# bionic_glove_1_01.net
KiCad netlist of a schematic drawn in EAGLE
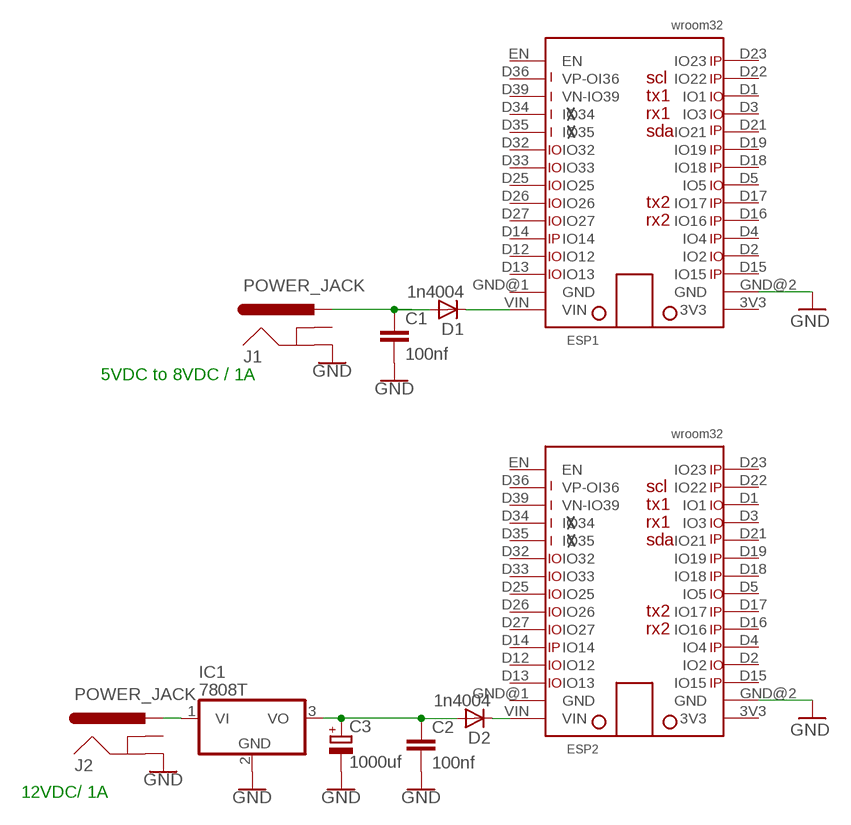
[diagram p0: schematic, sheet 1]

(export (version "E")
  (design (tool "Eeschema 10.0.6"))
  (components
    (comp (ref "C1")
      (value "100nf")
      (footprint "eagle-import:C1206")
      (libsource (lib "eagle-import") (part "CAPACITORC1206"))
    )
    (comp (ref "C2")
      (value "100nf")
      (footprint "eagle-import:C1206")
      (libsource (lib "eagle-import") (part "CAPACITORC1206"))
    )
    (comp (ref "C3")
      (value "1000uf")
      (footprint "eagle-import:E2,5-5")
      (libsource (lib "eagle-import") (part "CPOL-EUE2.5-5"))
    )
    (comp (ref "D1")
      (value "1n4004")
      (footprint "eagle-import:DIODE_DO35-7")
      (libsource (lib "eagle-import") (part "DIODE_E-DO35-7"))
    )
    (comp (ref "D2")
      (value "1n4004")
      (footprint "eagle-import:DIODE_DO35-7")
      (libsource (lib "eagle-import") (part "DIODE_E-DO35-7"))
    )
    (comp (ref "ESP1")
      (value "wroom32")
      (footprint "eagle-import:ESP32-DEVKITV1")
      (libsource (lib "eagle-import") (part "ESP32DEVKITV1"))
    )
    (comp (ref "ESP2")
      (value "wroom32")
      (footprint "eagle-import:ESP32-DEVKITV1")
      (libsource (lib "eagle-import") (part "ESP32DEVKITV1"))
    )
    (comp (ref "IC1")
      (value "7808T")
      (footprint "eagle-import:TO220H")
      (libsource (lib "eagle-import") (part "78T08"))
    )
    (comp (ref "J1")
      (value "POWER_JACK")
      (footprint "eagle-import:POWER_JACK_PTH")
      (libsource (lib "eagle-import") (part "POWER_JACK"))
    )
    (comp (ref "J2")
      (value "POWER_JACK")
      (footprint "eagle-import:POWER_JACK_PTH")
      (libsource (lib "eagle-import") (part "POWER_JACK"))
    )
  )
  (nets
    (net (code "1") (name "GND") (class "Default")
      (node (ref "C1") (pin "2") (pinfunction "2_2") (pintype "passive"))
      (node (ref "C2") (pin "2") (pinfunction "2_2") (pintype "passive"))
      (node (ref "C3") (pin "-") (pinfunction "-_-") (pintype "passive"))
      (node (ref "ESP1") (pin "GND@2") (pinfunction "GND_GND@2") (pintype "bidirectional"))
      (node (ref "ESP2") (pin "GND@2") (pinfunction "GND_GND@2") (pintype "bidirectional"))
      (node (ref "IC1") (pin "2") (pinfunction "GND_2") (pintype "passive"))
      (node (ref "J1") (pin "GND") (pinfunction "GND_GND") (pintype "bidirectional"))
      (node (ref "J2") (pin "GND") (pinfunction "GND_GND") (pintype "bidirectional"))
    )
    (net (code "2") (name "Net-(D1-A)") (class "Default")
      (node (ref "D1") (pin "C") (pinfunction "A_C") (pintype "passive"))
      (node (ref "ESP1") (pin "VIN") (pinfunction "VIN_VIN") (pintype "bidirectional"))
    )
    (net (code "3") (name "Net-(D1-C)") (class "Default")
      (node (ref "C1") (pin "1") (pinfunction "1_1") (pintype "passive"))
      (node (ref "D1") (pin "A") (pinfunction "C_A") (pintype "passive"))
      (node (ref "J1") (pin "PWR") (pinfunction "PWR_PWR") (pintype "bidirectional"))
    )
    (net (code "4") (name "Net-(D2-A)") (class "Default")
      (node (ref "D2") (pin "C") (pinfunction "A_C") (pintype "passive"))
      (node (ref "ESP2") (pin "VIN") (pinfunction "VIN_VIN") (pintype "bidirectional"))
    )
    (net (code "5") (name "Net-(D2-C)") (class "Default")
      (node (ref "C2") (pin "1") (pinfunction "1_1") (pintype "passive"))
      (node (ref "C3") (pin "+") (pinfunction "+_+") (pintype "passive"))
      (node (ref "D2") (pin "A") (pinfunction "C_A") (pintype "passive"))
      (node (ref "IC1") (pin "3") (pinfunction "VO_3") (pintype "passive"))
    )
    (net (code "6") (name "Net-(IC1-VI)") (class "Default")
      (node (ref "IC1") (pin "1") (pinfunction "VI_1") (pintype "input"))
      (node (ref "J2") (pin "PWR") (pinfunction "PWR_PWR") (pintype "bidirectional"))
    )
    (net (code "7") (name "unconnected-(ESP1-GND-PadGND@1)") (class "Default")
      (node (ref "ESP1") (pin "GND@1") (pinfunction "GND_GND@1") (pintype "bidirectional"))
    )
    (net (code "8") (name "unconnected-(ESP1-IO1-PadD1)") (class "Default")
      (node (ref "ESP1") (pin "D1") (pinfunction "IO1_D1") (pintype "bidirectional"))
    )
    (net (code "9") (name "unconnected-(ESP1-IO2-PadD2)") (class "Default")
      (node (ref "ESP1") (pin "D2") (pinfunction "IO2_D2") (pintype "bidirectional"))
    )
    (net (code "10") (name "unconnected-(ESP1-IO3-PadD3)") (class "Default")
      (node (ref "ESP1") (pin "D3") (pinfunction "IO3_D3") (pintype "bidirectional"))
    )
    (net (code "11") (name "unconnected-(ESP1-IO4-PadD4)") (class "Default")
      (node (ref "ESP1") (pin "D4") (pinfunction "IO4_D4") (pintype "bidirectional"))
    )
    (net (code "12") (name "unconnected-(ESP1-IO5-PadD5)") (class "Default")
      (node (ref "ESP1") (pin "D5") (pinfunction "IO5_D5") (pintype "bidirectional"))
    )
    (net (code "13") (name "unconnected-(ESP1-IO12-PadD12)") (class "Default")
      (node (ref "ESP1") (pin "D12") (pinfunction "IO12_D12") (pintype "bidirectional"))
    )
    (net (code "14") (name "unconnected-(ESP1-IO13-PadD13)") (class "Default")
      (node (ref "ESP1") (pin "D13") (pinfunction "IO13_D13") (pintype "bidirectional"))
    )
    (net (code "15") (name "unconnected-(ESP1-IO14-PadD14)") (class "Default")
      (node (ref "ESP1") (pin "D14") (pinfunction "IO14_D14") (pintype "bidirectional"))
    )
    (net (code "16") (name "unconnected-(ESP1-IO15-PadD15)") (class "Default")
      (node (ref "ESP1") (pin "D15") (pinfunction "IO15_D15") (pintype "bidirectional"))
    )
    (net (code "17") (name "unconnected-(ESP1-IO16-PadD16)") (class "Default")
      (node (ref "ESP1") (pin "D16") (pinfunction "IO16_D16") (pintype "bidirectional"))
    )
    (net (code "18") (name "unconnected-(ESP1-IO17-PadD17)") (class "Default")
      (node (ref "ESP1") (pin "D17") (pinfunction "IO17_D17") (pintype "bidirectional"))
    )
    (net (code "19") (name "unconnected-(ESP1-IO18-PadD18)") (class "Default")
      (node (ref "ESP1") (pin "D18") (pinfunction "IO18_D18") (pintype "bidirectional"))
    )
    (net (code "20") (name "unconnected-(ESP1-IO19-PadD19)") (class "Default")
      (node (ref "ESP1") (pin "D19") (pinfunction "IO19_D19") (pintype "bidirectional"))
    )
    (net (code "21") (name "unconnected-(ESP1-IO21-PadD21)") (class "Default")
      (node (ref "ESP1") (pin "D21") (pinfunction "IO21_D21") (pintype "bidirectional"))
    )
    (net (code "22") (name "unconnected-(ESP1-IO22-PadD22)") (class "Default")
      (node (ref "ESP1") (pin "D22") (pinfunction "IO22_D22") (pintype "bidirectional"))
    )
    (net (code "23") (name "unconnected-(ESP1-IO23-PadD23)") (class "Default")
      (node (ref "ESP1") (pin "D23") (pinfunction "IO23_D23") (pintype "bidirectional"))
    )
    (net (code "24") (name "unconnected-(ESP1-IO25-PadD25)") (class "Default")
      (node (ref "ESP1") (pin "D25") (pinfunction "IO25_D25") (pintype "bidirectional"))
    )
    (net (code "25") (name "unconnected-(ESP1-IO26-PadD26)") (class "Default")
      (node (ref "ESP1") (pin "D26") (pinfunction "IO26_D26") (pintype "bidirectional"))
    )
    (net (code "26") (name "unconnected-(ESP1-IO27-PadD27)") (class "Default")
      (node (ref "ESP1") (pin "D27") (pinfunction "IO27_D27") (pintype "bidirectional"))
    )
    (net (code "27") (name "unconnected-(ESP1-IO32-PadD32)") (class "Default")
      (node (ref "ESP1") (pin "D32") (pinfunction "IO32_D32") (pintype "bidirectional"))
    )
    (net (code "28") (name "unconnected-(ESP1-IO33-PadD33)") (class "Default")
      (node (ref "ESP1") (pin "D33") (pinfunction "IO33_D33") (pintype "bidirectional"))
    )
    (net (code "29") (name "unconnected-(ESP1-IO34-PadD34)") (class "Default")
      (node (ref "ESP1") (pin "D34") (pinfunction "IO34_D34") (pintype "bidirectional"))
    )
    (net (code "30") (name "unconnected-(ESP1-IO35-PadD35)") (class "Default")
      (node (ref "ESP1") (pin "D35") (pinfunction "IO35_D35") (pintype "bidirectional"))
    )
    (net (code "31") (name "unconnected-(ESP1-Pad3V3)") (class "Default")
      (node (ref "ESP1") (pin "3V3") (pinfunction "3V3_3V3") (pintype "bidirectional"))
    )
    (net (code "32") (name "unconnected-(ESP1-PadEN)") (class "Default")
      (node (ref "ESP1") (pin "EN") (pinfunction "EN_EN") (pintype "bidirectional"))
    )
    (net (code "33") (name "unconnected-(ESP1-VN-IO39-PadD39)") (class "Default")
      (node (ref "ESP1") (pin "D39") (pinfunction "VN-IO39_D39") (pintype "bidirectional"))
    )
    (net (code "34") (name "unconnected-(ESP1-VP-OI36-PadD36)") (class "Default")
      (node (ref "ESP1") (pin "D36") (pinfunction "VP-OI36_D36") (pintype "bidirectional"))
    )
    (net (code "35") (name "unconnected-(ESP2-GND-PadGND@1)") (class "Default")
      (node (ref "ESP2") (pin "GND@1") (pinfunction "GND_GND@1") (pintype "bidirectional"))
    )
    (net (code "36") (name "unconnected-(ESP2-IO1-PadD1)") (class "Default")
      (node (ref "ESP2") (pin "D1") (pinfunction "IO1_D1") (pintype "bidirectional"))
    )
    (net (code "37") (name "unconnected-(ESP2-IO2-PadD2)") (class "Default")
      (node (ref "ESP2") (pin "D2") (pinfunction "IO2_D2") (pintype "bidirectional"))
    )
    (net (code "38") (name "unconnected-(ESP2-IO3-PadD3)") (class "Default")
      (node (ref "ESP2") (pin "D3") (pinfunction "IO3_D3") (pintype "bidirectional"))
    )
    (net (code "39") (name "unconnected-(ESP2-IO4-PadD4)") (class "Default")
      (node (ref "ESP2") (pin "D4") (pinfunction "IO4_D4") (pintype "bidirectional"))
    )
    (net (code "40") (name "unconnected-(ESP2-IO5-PadD5)") (class "Default")
      (node (ref "ESP2") (pin "D5") (pinfunction "IO5_D5") (pintype "bidirectional"))
    )
    (net (code "41") (name "unconnected-(ESP2-IO12-PadD12)") (class "Default")
      (node (ref "ESP2") (pin "D12") (pinfunction "IO12_D12") (pintype "bidirectional"))
    )
    (net (code "42") (name "unconnected-(ESP2-IO13-PadD13)") (class "Default")
      (node (ref "ESP2") (pin "D13") (pinfunction "IO13_D13") (pintype "bidirectional"))
    )
    (net (code "43") (name "unconnected-(ESP2-IO14-PadD14)") (class "Default")
      (node (ref "ESP2") (pin "D14") (pinfunction "IO14_D14") (pintype "bidirectional"))
    )
    (net (code "44") (name "unconnected-(ESP2-IO15-PadD15)") (class "Default")
      (node (ref "ESP2") (pin "D15") (pinfunction "IO15_D15") (pintype "bidirectional"))
    )
    (net (code "45") (name "unconnected-(ESP2-IO16-PadD16)") (class "Default")
      (node (ref "ESP2") (pin "D16") (pinfunction "IO16_D16") (pintype "bidirectional"))
    )
    (net (code "46") (name "unconnected-(ESP2-IO17-PadD17)") (class "Default")
      (node (ref "ESP2") (pin "D17") (pinfunction "IO17_D17") (pintype "bidirectional"))
    )
    (net (code "47") (name "unconnected-(ESP2-IO18-PadD18)") (class "Default")
      (node (ref "ESP2") (pin "D18") (pinfunction "IO18_D18") (pintype "bidirectional"))
    )
    (net (code "48") (name "unconnected-(ESP2-IO19-PadD19)") (class "Default")
      (node (ref "ESP2") (pin "D19") (pinfunction "IO19_D19") (pintype "bidirectional"))
    )
    (net (code "49") (name "unconnected-(ESP2-IO21-PadD21)") (class "Default")
      (node (ref "ESP2") (pin "D21") (pinfunction "IO21_D21") (pintype "bidirectional"))
    )
    (net (code "50") (name "unconnected-(ESP2-IO22-PadD22)") (class "Default")
      (node (ref "ESP2") (pin "D22") (pinfunction "IO22_D22") (pintype "bidirectional"))
    )
    (net (code "51") (name "unconnected-(ESP2-IO23-PadD23)") (class "Default")
      (node (ref "ESP2") (pin "D23") (pinfunction "IO23_D23") (pintype "bidirectional"))
    )
    (net (code "52") (name "unconnected-(ESP2-IO25-PadD25)") (class "Default")
      (node (ref "ESP2") (pin "D25") (pinfunction "IO25_D25") (pintype "bidirectional"))
    )
    (net (code "53") (name "unconnected-(ESP2-IO26-PadD26)") (class "Default")
      (node (ref "ESP2") (pin "D26") (pinfunction "IO26_D26") (pintype "bidirectional"))
    )
    (net (code "54") (name "unconnected-(ESP2-IO27-PadD27)") (class "Default")
      (node (ref "ESP2") (pin "D27") (pinfunction "IO27_D27") (pintype "bidirectional"))
    )
    (net (code "55") (name "unconnected-(ESP2-IO32-PadD32)") (class "Default")
      (node (ref "ESP2") (pin "D32") (pinfunction "IO32_D32") (pintype "bidirectional"))
    )
    (net (code "56") (name "unconnected-(ESP2-IO33-PadD33)") (class "Default")
      (node (ref "ESP2") (pin "D33") (pinfunction "IO33_D33") (pintype "bidirectional"))
    )
    (net (code "57") (name "unconnected-(ESP2-IO34-PadD34)") (class "Default")
      (node (ref "ESP2") (pin "D34") (pinfunction "IO34_D34") (pintype "bidirectional"))
    )
    (net (code "58") (name "unconnected-(ESP2-IO35-PadD35)") (class "Default")
      (node (ref "ESP2") (pin "D35") (pinfunction "IO35_D35") (pintype "bidirectional"))
    )
    (net (code "59") (name "unconnected-(ESP2-Pad3V3)") (class "Default")
      (node (ref "ESP2") (pin "3V3") (pinfunction "3V3_3V3") (pintype "bidirectional"))
    )
    (net (code "60") (name "unconnected-(ESP2-PadEN)") (class "Default")
      (node (ref "ESP2") (pin "EN") (pinfunction "EN_EN") (pintype "bidirectional"))
    )
    (net (code "61") (name "unconnected-(ESP2-VN-IO39-PadD39)") (class "Default")
      (node (ref "ESP2") (pin "D39") (pinfunction "VN-IO39_D39") (pintype "bidirectional"))
    )
    (net (code "62") (name "unconnected-(ESP2-VP-OI36-PadD36)") (class "Default")
      (node (ref "ESP2") (pin "D36") (pinfunction "VP-OI36_D36") (pintype "bidirectional"))
    )
    (net (code "63") (name "unconnected-(J1-PadGNDBREAK)") (class "Default")
      (node (ref "J1") (pin "GNDBREAK") (pinfunction "GNDBREAK_GNDBREAK") (pintype "bidirectional"))
    )
    (net (code "64") (name "unconnected-(J2-PadGNDBREAK)") (class "Default")
      (node (ref "J2") (pin "GNDBREAK") (pinfunction "GNDBREAK_GNDBREAK") (pintype "bidirectional"))
    )
  )
)
